# Attenuverting_LinExp_VCA_Top.net
KiCad netlist of a schematic drawn in EAGLE
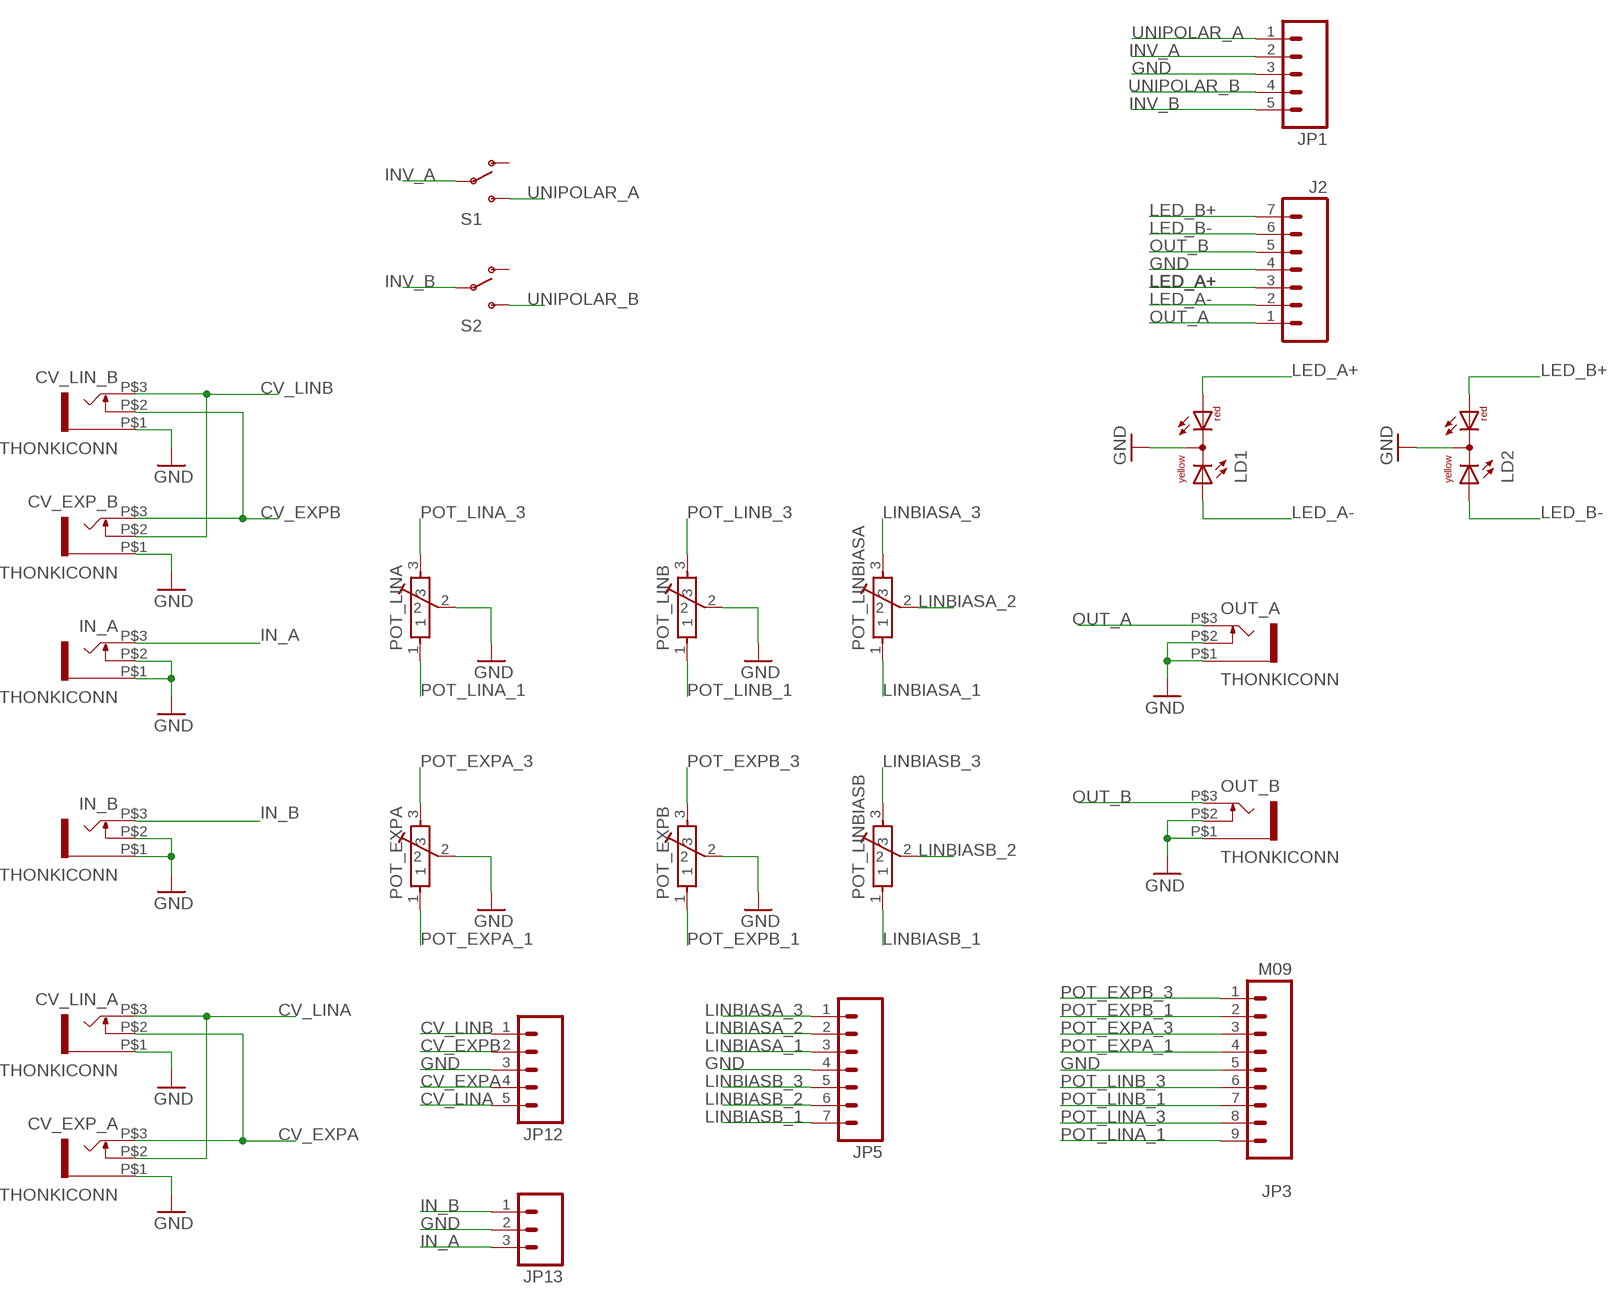
[diagram p0: schematic, sheet 1]

(export (version "E")
  (design (tool "Eeschema 10.0.6"))
  (components
    (comp (ref "CV_EXP_A")
      (value "THONKICONN")
      (footprint "eagle-import:THONKICONN")
      (libsource (lib "eagle-import") (part "THONKICONN"))
    )
    (comp (ref "CV_EXP_B")
      (value "THONKICONN")
      (footprint "eagle-import:THONKICONN")
      (libsource (lib "eagle-import") (part "THONKICONN"))
    )
    (comp (ref "CV_LIN_A")
      (value "THONKICONN")
      (footprint "eagle-import:THONKICONN")
      (libsource (lib "eagle-import") (part "THONKICONN"))
    )
    (comp (ref "CV_LIN_B")
      (value "THONKICONN")
      (footprint "eagle-import:THONKICONN")
      (libsource (lib "eagle-import") (part "THONKICONN"))
    )
    (comp (ref "IN_A")
      (value "THONKICONN")
      (footprint "eagle-import:THONKICONN")
      (libsource (lib "eagle-import") (part "THONKICONN"))
    )
    (comp (ref "IN_B")
      (value "THONKICONN")
      (footprint "eagle-import:THONKICONN")
      (libsource (lib "eagle-import") (part "THONKICONN"))
    )
    (comp (ref "J2")
      (value "M07")
      (footprint "eagle-import:1X07")
      (libsource (lib "eagle-import") (part "M07"))
    )
    (comp (ref "JP1")
      (value "M05PTH")
      (footprint "eagle-import:1X05")
      (libsource (lib "eagle-import") (part "M05PTH"))
    )
    (comp (ref "JP3")
      (value "M09")
      (footprint "eagle-import:1X09")
      (libsource (lib "eagle-import") (part "M09"))
    )
    (comp (ref "JP5")
      (value "M07")
      (footprint "eagle-import:1X07")
      (libsource (lib "eagle-import") (part "M07"))
    )
    (comp (ref "JP12")
      (value "M05PTH")
      (footprint "eagle-import:1X05")
      (libsource (lib "eagle-import") (part "M05PTH"))
    )
    (comp (ref "JP13")
      (value "M03PTH")
      (footprint "eagle-import:1X03")
      (libsource (lib "eagle-import") (part "M03PTH"))
    )
    (comp (ref "LD1")
      (value "DUOLED-RY-C")
      (footprint "eagle-import:DUOLED-C-5MM")
      (libsource (lib "eagle-import") (part "DUOLED-RY-C"))
    )
    (comp (ref "LD2")
      (value "DUOLED-RY-C")
      (footprint "eagle-import:DUOLED-C-5MM")
      (libsource (lib "eagle-import") (part "DUOLED-RY-C"))
    )
    (comp (ref "OUT_A")
      (value "THONKICONN")
      (footprint "eagle-import:THONKICONN")
      (libsource (lib "eagle-import") (part "THONKICONN"))
    )
    (comp (ref "OUT_B")
      (value "THONKICONN")
      (footprint "eagle-import:THONKICONN")
      (libsource (lib "eagle-import") (part "THONKICONN"))
    )
    (comp (ref "POT_EXPA")
      (value "POT-ALPS-RK09L1140")
      (footprint "eagle-import:POT-ALPS-RK09L1140")
      (libsource (lib "eagle-import") (part "POT-ALPS-RK09L1140"))
    )
    (comp (ref "POT_EXPB")
      (value "POT-ALPS-RK09L1140")
      (footprint "eagle-import:POT-ALPS-RK09L1140")
      (libsource (lib "eagle-import") (part "POT-ALPS-RK09L1140"))
    )
    (comp (ref "POT_LINA")
      (value "POT-ALPS-RK09L1140")
      (footprint "eagle-import:POT-ALPS-RK09L1140")
      (libsource (lib "eagle-import") (part "POT-ALPS-RK09L1140"))
    )
    (comp (ref "POT_LINB")
      (value "POT-ALPS-RK09L1140")
      (footprint "eagle-import:POT-ALPS-RK09L1140")
      (libsource (lib "eagle-import") (part "POT-ALPS-RK09L1140"))
    )
    (comp (ref "POT_LINBIASA")
      (value "POT-ALPS-RK09L1140")
      (footprint "eagle-import:POT-ALPS-RK09L1140")
      (libsource (lib "eagle-import") (part "POT-ALPS-RK09L1140"))
    )
    (comp (ref "POT_LINBIASB")
      (value "POT-ALPS-RK09L1140")
      (footprint "eagle-import:POT-ALPS-RK09L1140")
      (libsource (lib "eagle-import") (part "POT-ALPS-RK09L1140"))
    )
    (comp (ref "S1")
      (value "SWITCH-SPST")
      (footprint "eagle-import:SWITCH-SPDT-SALECOM-T8014")
      (libsource (lib "eagle-import") (part "SWITCH-SPST"))
    )
    (comp (ref "S2")
      (value "SWITCH-SPST")
      (footprint "eagle-import:SWITCH-SPDT-SALECOM-T8014")
      (libsource (lib "eagle-import") (part "SWITCH-SPST"))
    )
  )
  (nets
    (net (code "1") (name "/CV_EXPA") (class "Default")
      (node (ref "CV_EXP_A") (pin "P$3") (pinfunction "3_P$3") (pintype "passive"))
      (node (ref "CV_LIN_A") (pin "P$2") (pinfunction "4_P$2") (pintype "passive"))
      (node (ref "JP12") (pin "4") (pinfunction "4_4") (pintype "passive"))
    )
    (net (code "2") (name "/CV_EXPB") (class "Default")
      (node (ref "CV_EXP_B") (pin "P$3") (pinfunction "3_P$3") (pintype "passive"))
      (node (ref "CV_LIN_B") (pin "P$2") (pinfunction "4_P$2") (pintype "passive"))
      (node (ref "JP12") (pin "2") (pinfunction "2_2") (pintype "passive"))
    )
    (net (code "3") (name "/CV_LINA") (class "Default")
      (node (ref "CV_EXP_A") (pin "P$2") (pinfunction "4_P$2") (pintype "passive"))
      (node (ref "CV_LIN_A") (pin "P$3") (pinfunction "3_P$3") (pintype "passive"))
      (node (ref "JP12") (pin "5") (pinfunction "5_5") (pintype "passive"))
    )
    (net (code "4") (name "/CV_LINB") (class "Default")
      (node (ref "CV_EXP_B") (pin "P$2") (pinfunction "4_P$2") (pintype "passive"))
      (node (ref "CV_LIN_B") (pin "P$3") (pinfunction "3_P$3") (pintype "passive"))
      (node (ref "JP12") (pin "1") (pinfunction "1_1") (pintype "passive"))
    )
    (net (code "5") (name "/INV_A") (class "Default")
      (node (ref "JP1") (pin "2") (pinfunction "2_2") (pintype "passive"))
      (node (ref "S1") (pin "2") (pinfunction "P_2") (pintype "passive"))
    )
    (net (code "6") (name "/INV_B") (class "Default")
      (node (ref "JP1") (pin "5") (pinfunction "5_5") (pintype "passive"))
      (node (ref "S2") (pin "2") (pinfunction "P_2") (pintype "passive"))
    )
    (net (code "7") (name "/IN_A") (class "Default")
      (node (ref "IN_A") (pin "P$3") (pinfunction "3_P$3") (pintype "passive"))
      (node (ref "JP13") (pin "3") (pinfunction "3_3") (pintype "passive"))
    )
    (net (code "8") (name "/IN_B") (class "Default")
      (node (ref "IN_B") (pin "P$3") (pinfunction "3_P$3") (pintype "passive"))
      (node (ref "JP13") (pin "1") (pinfunction "1_1") (pintype "passive"))
    )
    (net (code "9") (name "/LED_A+") (class "Default")
      (node (ref "J2") (pin "3") (pinfunction "3_3") (pintype "passive"))
      (node (ref "LD1") (pin "AR") (pinfunction "AR_AR") (pintype "passive"))
    )
    (net (code "10") (name "/LED_A-") (class "Default")
      (node (ref "J2") (pin "2") (pinfunction "2_2") (pintype "passive"))
      (node (ref "LD1") (pin "AX") (pinfunction "AY_AX") (pintype "passive"))
    )
    (net (code "11") (name "/LED_B+") (class "Default")
      (node (ref "J2") (pin "7") (pinfunction "7_7") (pintype "passive"))
      (node (ref "LD2") (pin "AR") (pinfunction "AR_AR") (pintype "passive"))
    )
    (net (code "12") (name "/LED_B-") (class "Default")
      (node (ref "J2") (pin "6") (pinfunction "6_6") (pintype "passive"))
      (node (ref "LD2") (pin "AX") (pinfunction "AY_AX") (pintype "passive"))
    )
    (net (code "13") (name "/LINBIASA_1") (class "Default")
      (node (ref "JP5") (pin "3") (pinfunction "3_3") (pintype "passive"))
      (node (ref "POT_LINBIASA") (pin "1") (pinfunction "1_1") (pintype "bidirectional"))
    )
    (net (code "14") (name "/LINBIASA_2") (class "Default")
      (node (ref "JP5") (pin "2") (pinfunction "2_2") (pintype "passive"))
      (node (ref "POT_LINBIASA") (pin "2") (pinfunction "2_2") (pintype "bidirectional"))
    )
    (net (code "15") (name "/LINBIASA_3") (class "Default")
      (node (ref "JP5") (pin "1") (pinfunction "1_1") (pintype "passive"))
      (node (ref "POT_LINBIASA") (pin "3") (pinfunction "3_3") (pintype "bidirectional"))
    )
    (net (code "16") (name "/LINBIASB_1") (class "Default")
      (node (ref "JP5") (pin "7") (pinfunction "7_7") (pintype "passive"))
      (node (ref "POT_LINBIASB") (pin "1") (pinfunction "1_1") (pintype "bidirectional"))
    )
    (net (code "17") (name "/LINBIASB_2") (class "Default")
      (node (ref "JP5") (pin "6") (pinfunction "6_6") (pintype "passive"))
      (node (ref "POT_LINBIASB") (pin "2") (pinfunction "2_2") (pintype "bidirectional"))
    )
    (net (code "18") (name "/LINBIASB_3") (class "Default")
      (node (ref "JP5") (pin "5") (pinfunction "5_5") (pintype "passive"))
      (node (ref "POT_LINBIASB") (pin "3") (pinfunction "3_3") (pintype "bidirectional"))
    )
    (net (code "19") (name "/OUT_A") (class "Default")
      (node (ref "J2") (pin "1") (pinfunction "1_1") (pintype "passive"))
      (node (ref "OUT_A") (pin "P$3") (pinfunction "3_P$3") (pintype "passive"))
    )
    (net (code "20") (name "/OUT_B") (class "Default")
      (node (ref "J2") (pin "5") (pinfunction "5_5") (pintype "passive"))
      (node (ref "OUT_B") (pin "P$3") (pinfunction "3_P$3") (pintype "passive"))
    )
    (net (code "21") (name "/POT_EXPA_1") (class "Default")
      (node (ref "JP3") (pin "4") (pinfunction "4_4") (pintype "passive"))
      (node (ref "POT_EXPA") (pin "1") (pinfunction "1_1") (pintype "bidirectional"))
    )
    (net (code "22") (name "/POT_EXPA_3") (class "Default")
      (node (ref "JP3") (pin "3") (pinfunction "3_3") (pintype "passive"))
      (node (ref "POT_EXPA") (pin "3") (pinfunction "3_3") (pintype "bidirectional"))
    )
    (net (code "23") (name "/POT_EXPB_1") (class "Default")
      (node (ref "JP3") (pin "2") (pinfunction "2_2") (pintype "passive"))
      (node (ref "POT_EXPB") (pin "1") (pinfunction "1_1") (pintype "bidirectional"))
    )
    (net (code "24") (name "/POT_EXPB_3") (class "Default")
      (node (ref "JP3") (pin "1") (pinfunction "1_1") (pintype "passive"))
      (node (ref "POT_EXPB") (pin "3") (pinfunction "3_3") (pintype "bidirectional"))
    )
    (net (code "25") (name "/POT_LINA_1") (class "Default")
      (node (ref "JP3") (pin "9") (pinfunction "9_9") (pintype "passive"))
      (node (ref "POT_LINA") (pin "1") (pinfunction "1_1") (pintype "bidirectional"))
    )
    (net (code "26") (name "/POT_LINA_3") (class "Default")
      (node (ref "JP3") (pin "8") (pinfunction "8_8") (pintype "passive"))
      (node (ref "POT_LINA") (pin "3") (pinfunction "3_3") (pintype "bidirectional"))
    )
    (net (code "27") (name "/POT_LINB_1") (class "Default")
      (node (ref "JP3") (pin "7") (pinfunction "7_7") (pintype "passive"))
      (node (ref "POT_LINB") (pin "1") (pinfunction "1_1") (pintype "bidirectional"))
    )
    (net (code "28") (name "/POT_LINB_3") (class "Default")
      (node (ref "JP3") (pin "6") (pinfunction "6_6") (pintype "passive"))
      (node (ref "POT_LINB") (pin "3") (pinfunction "3_3") (pintype "bidirectional"))
    )
    (net (code "29") (name "/UNIPOLAR_A") (class "Default")
      (node (ref "JP1") (pin "1") (pinfunction "1_1") (pintype "passive"))
      (node (ref "S1") (pin "3") (pinfunction "S_3") (pintype "passive"))
    )
    (net (code "30") (name "/UNIPOLAR_B") (class "Default")
      (node (ref "JP1") (pin "4") (pinfunction "4_4") (pintype "passive"))
      (node (ref "S2") (pin "3") (pinfunction "S_3") (pintype "passive"))
    )
    (net (code "31") (name "GND") (class "Default")
      (node (ref "CV_EXP_A") (pin "P$1") (pinfunction "5_P$1") (pintype "passive"))
      (node (ref "CV_EXP_B") (pin "P$1") (pinfunction "5_P$1") (pintype "passive"))
      (node (ref "CV_LIN_A") (pin "P$1") (pinfunction "5_P$1") (pintype "passive"))
      (node (ref "CV_LIN_B") (pin "P$1") (pinfunction "5_P$1") (pintype "passive"))
      (node (ref "IN_A") (pin "P$1") (pinfunction "5_P$1") (pintype "passive"))
      (node (ref "IN_A") (pin "P$2") (pinfunction "4_P$2") (pintype "passive"))
      (node (ref "IN_B") (pin "P$1") (pinfunction "5_P$1") (pintype "passive"))
      (node (ref "IN_B") (pin "P$2") (pinfunction "4_P$2") (pintype "passive"))
      (node (ref "J2") (pin "4") (pinfunction "4_4") (pintype "passive"))
      (node (ref "JP1") (pin "3") (pinfunction "3_3") (pintype "passive"))
      (node (ref "JP12") (pin "3") (pinfunction "3_3") (pintype "passive"))
      (node (ref "JP13") (pin "2") (pinfunction "2_2") (pintype "passive"))
      (node (ref "JP3") (pin "5") (pinfunction "5_5") (pintype "passive"))
      (node (ref "JP5") (pin "4") (pinfunction "4_4") (pintype "passive"))
      (node (ref "LD1") (pin "C") (pinfunction "C_C") (pintype "passive"))
      (node (ref "LD2") (pin "C") (pinfunction "C_C") (pintype "passive"))
      (node (ref "OUT_A") (pin "P$1") (pinfunction "5_P$1") (pintype "passive"))
      (node (ref "OUT_A") (pin "P$2") (pinfunction "4_P$2") (pintype "passive"))
      (node (ref "OUT_B") (pin "P$1") (pinfunction "5_P$1") (pintype "passive"))
      (node (ref "OUT_B") (pin "P$2") (pinfunction "4_P$2") (pintype "passive"))
      (node (ref "POT_EXPA") (pin "2") (pinfunction "2_2") (pintype "bidirectional"))
      (node (ref "POT_EXPB") (pin "2") (pinfunction "2_2") (pintype "bidirectional"))
      (node (ref "POT_LINA") (pin "2") (pinfunction "2_2") (pintype "bidirectional"))
      (node (ref "POT_LINB") (pin "2") (pinfunction "2_2") (pintype "bidirectional"))
    )
    (net (code "32") (name "unconnected-(S1-O-Pad1)") (class "Default")
      (node (ref "S1") (pin "1") (pinfunction "O_1") (pintype "passive"))
    )
    (net (code "33") (name "unconnected-(S2-O-Pad1)") (class "Default")
      (node (ref "S2") (pin "1") (pinfunction "O_1") (pintype "passive"))
    )
  )
)
